# 8x_LED_Trieber_Stage_01.net
KiCad netlist of a schematic drawn in EAGLE
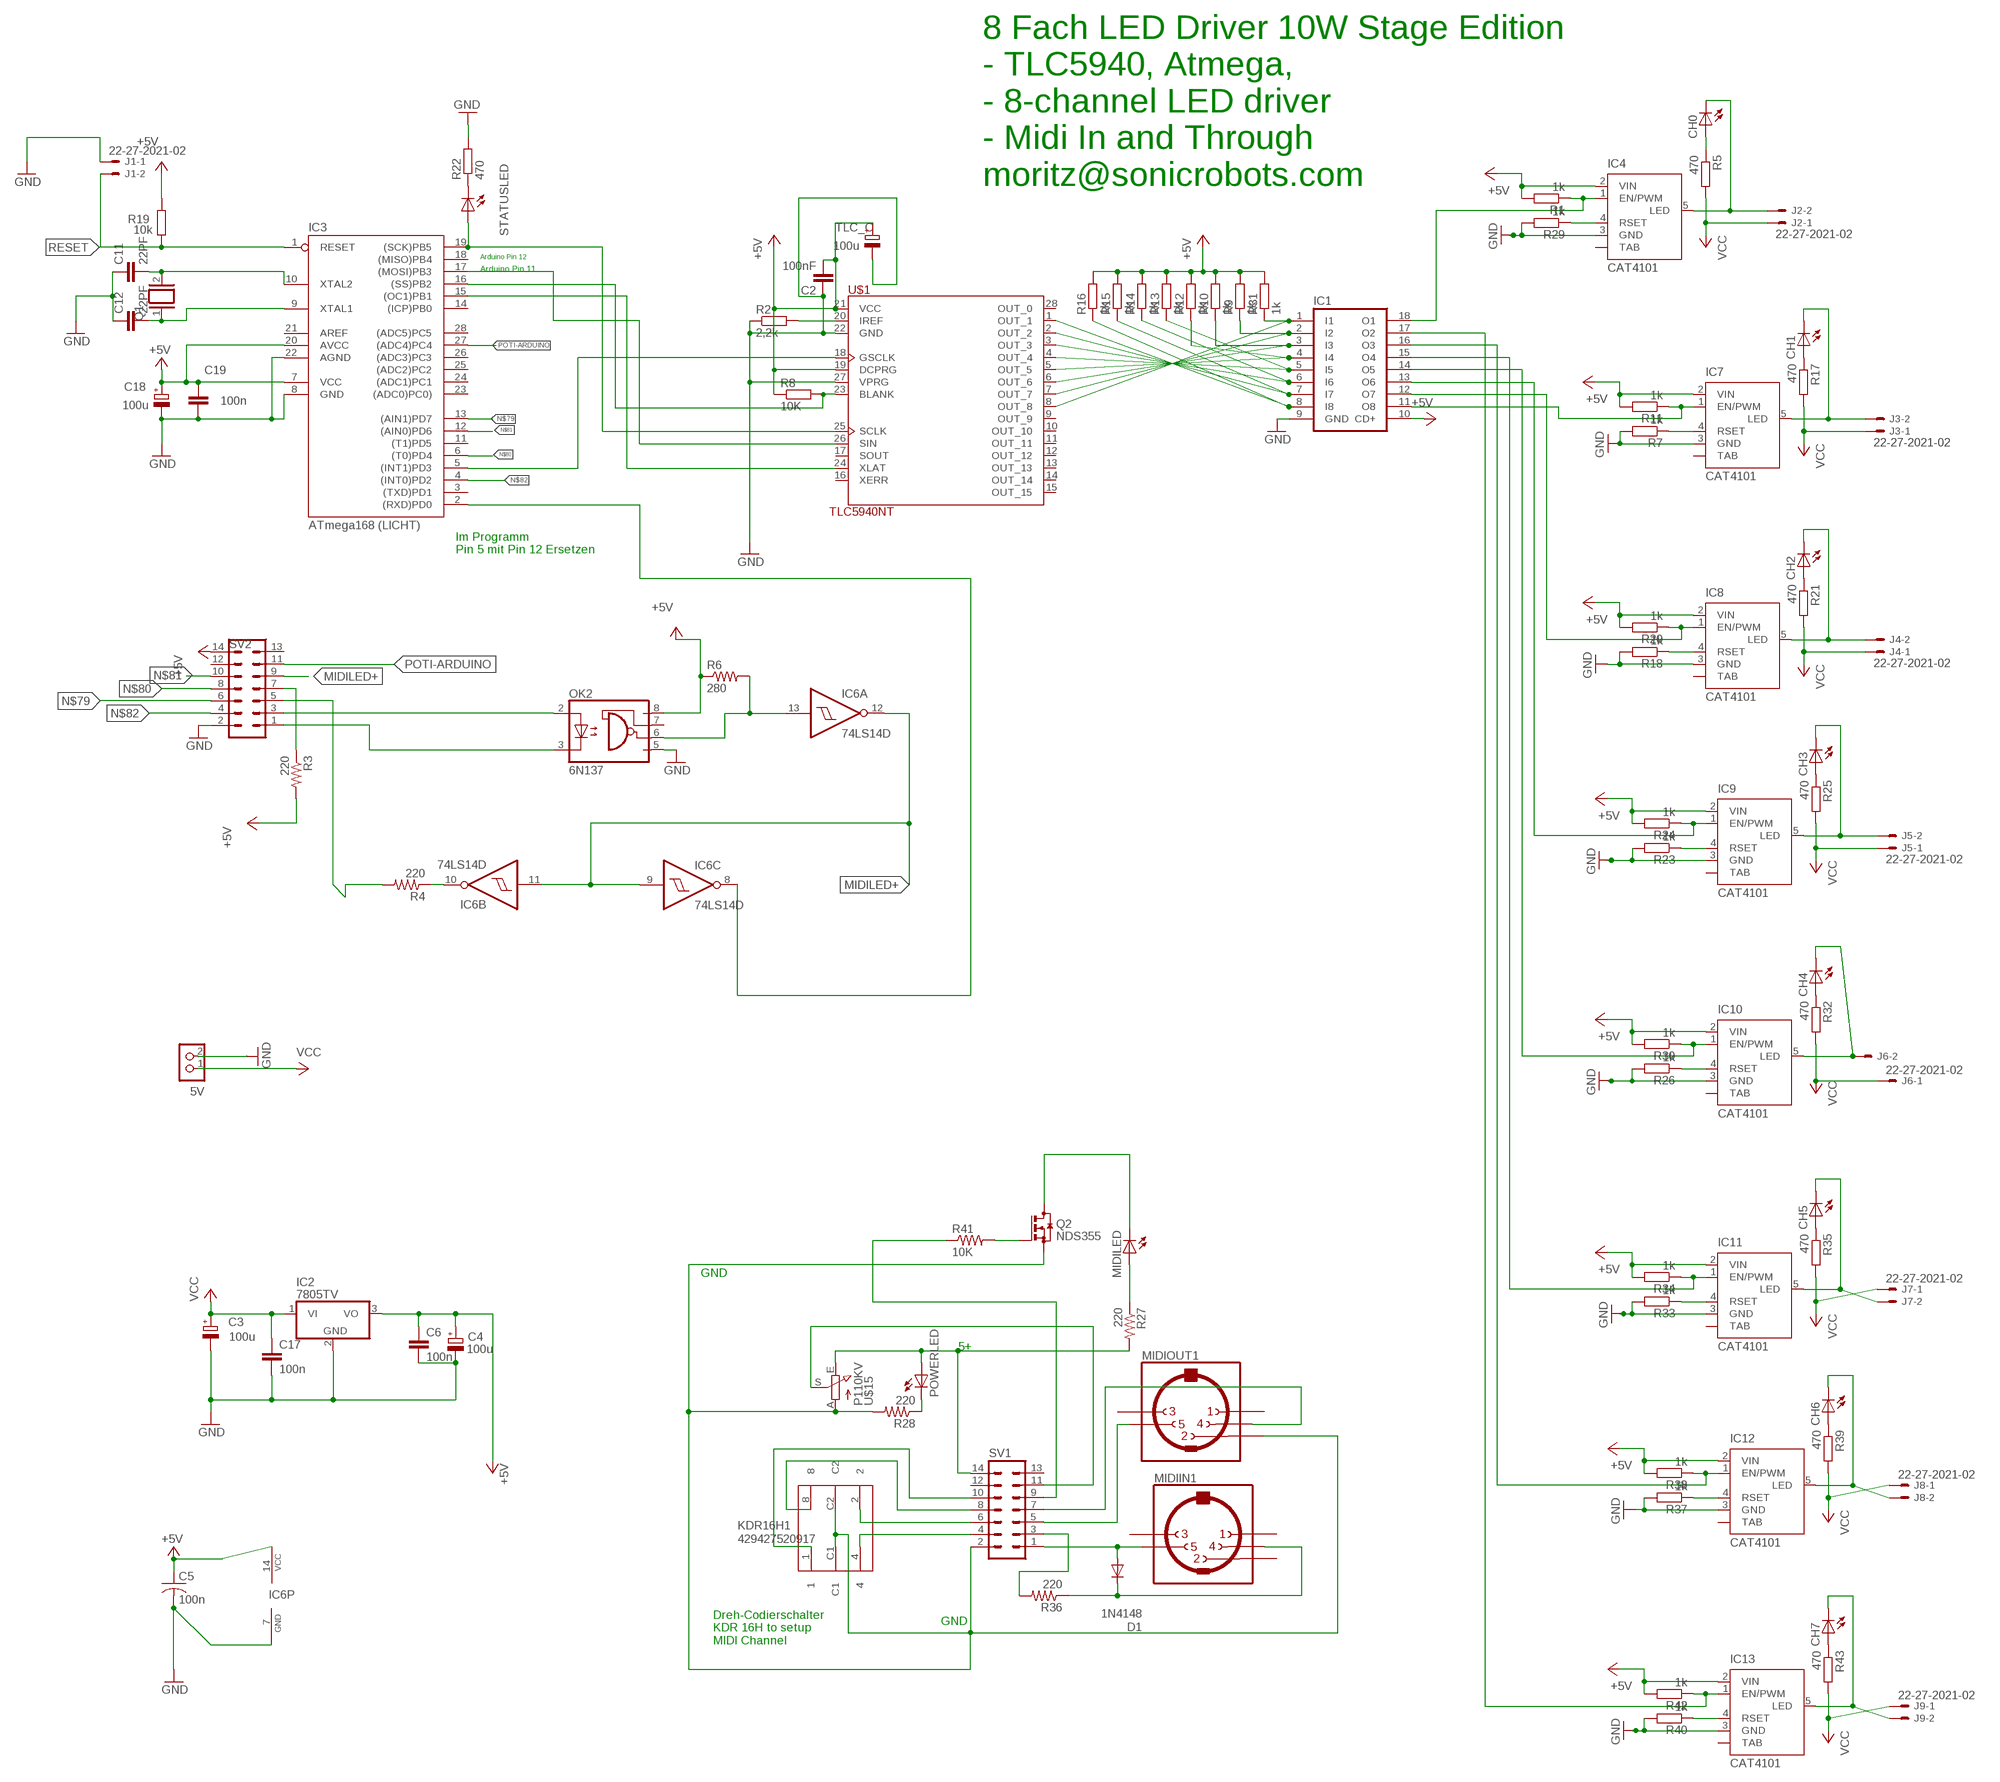
[diagram p0: schematic, sheet 1]

(export (version "E")
  (design (tool "Eeschema 10.0.6"))
  (components
    (comp (ref "5V")
      (value "5V")
      (footprint "eagle-import:TERMINAL_BLOCK_2P_5")
      (libsource (lib "eagle-import") (part "CON_TERMINAL_BLOCK_02-5MM"))
    )
    (comp (ref "C2")
      (value "100nF")
      (footprint "eagle-import:C0805")
      (libsource (lib "eagle-import") (part "rcl_C-EUC0805"))
    )
    (comp (ref "C3")
      (value "100u")
      (footprint "eagle-import:E2,5-6")
      (libsource (lib "eagle-import") (part "CPOL-EUE2.5-6"))
    )
    (comp (ref "C4")
      (value "100u")
      (footprint "eagle-import:E2,5-6")
      (libsource (lib "eagle-import") (part "CPOL-EUE2.5-6"))
    )
    (comp (ref "C5")
      (value "100n")
      (footprint "eagle-import:C0805")
      (libsource (lib "eagle-import") (part "C-USC0805"))
    )
    (comp (ref "C6")
      (value "100n")
      (footprint "eagle-import:C0805K")
      (libsource (lib "eagle-import") (part "C-EUC0805K"))
    )
    (comp (ref "C11")
      (value "22PF")
      (footprint "eagle-import:C0805")
      (libsource (lib "eagle-import") (part "rcl_C-EUC0805"))
    )
    (comp (ref "C12")
      (value "22PF")
      (footprint "eagle-import:C0805")
      (libsource (lib "eagle-import") (part "rcl_C-EUC0805"))
    )
    (comp (ref "C17")
      (value "100n")
      (footprint "eagle-import:C0805K")
      (libsource (lib "eagle-import") (part "C-EUC0805K"))
    )
    (comp (ref "C18")
      (value "100u")
      (footprint "eagle-import:E2,5-6")
      (libsource (lib "eagle-import") (part "CPOL-EUE2.5-6"))
    )
    (comp (ref "C19")
      (value "100n")
      (footprint "eagle-import:C0805K")
      (libsource (lib "eagle-import") (part "C-EUC0805K"))
    )
    (comp (ref "CH0")
      (value "LED3MM")
      (footprint "eagle-import:LED3MM")
      (libsource (lib "eagle-import") (part "LED3MM"))
    )
    (comp (ref "CH1")
      (value "LED3MM")
      (footprint "eagle-import:LED3MM")
      (libsource (lib "eagle-import") (part "LED3MM"))
    )
    (comp (ref "CH2")
      (value "LED3MM")
      (footprint "eagle-import:LED3MM")
      (libsource (lib "eagle-import") (part "LED3MM"))
    )
    (comp (ref "CH3")
      (value "LED3MM")
      (footprint "eagle-import:LED3MM")
      (libsource (lib "eagle-import") (part "LED3MM"))
    )
    (comp (ref "CH4")
      (value "LED3MM")
      (footprint "eagle-import:LED3MM")
      (libsource (lib "eagle-import") (part "LED3MM"))
    )
    (comp (ref "CH5")
      (value "LED3MM")
      (footprint "eagle-import:LED3MM")
      (libsource (lib "eagle-import") (part "LED3MM"))
    )
    (comp (ref "CH6")
      (value "LED3MM")
      (footprint "eagle-import:LED3MM")
      (libsource (lib "eagle-import") (part "LED3MM"))
    )
    (comp (ref "CH7")
      (value "LED3MM")
      (footprint "eagle-import:LED3MM")
      (libsource (lib "eagle-import") (part "LED3MM"))
    )
    (comp (ref "D1")
      (value "1N4148")
      (footprint "eagle-import:D-7.5")
      (libsource (lib "eagle-import") (part "DIODE-D-7.5"))
    )
    (comp (ref "IC1")
      (value "IC_ULN2803AN")
      (footprint "eagle-import:DIL18")
      (libsource (lib "eagle-import") (part "IC_ULN2803AN"))
    )
    (comp (ref "IC2")
      (value "7805TV")
      (footprint "eagle-import:TO220V")
      (libsource (lib "eagle-import") (part "78TV05"))
    )
    (comp (ref "IC3")
      (value "ATmega168 (LICHT)")
      (footprint "eagle-import:DIL28-3")
      (libsource (lib "eagle-import") (part "AT90S4433P"))
    )
    (comp (ref "IC4")
      (value "CAT4101")
      (footprint "eagle-import:TO263_5")
      (fields (field (name "MPN") "CAT4101TV-T75"))
      (libsource (lib "eagle-import") (part "CAT4101"))
    )
    (comp (ref "IC6")
      (value "74LS14D")
      (footprint "eagle-import:SO14")
      (libsource (lib "eagle-import") (part "7414DLS"))
    )
    (comp (ref "IC7")
      (value "CAT4101")
      (footprint "eagle-import:TO263_5")
      (fields (field (name "MPN") "CAT4101TV-T75"))
      (libsource (lib "eagle-import") (part "CAT4101"))
    )
    (comp (ref "IC8")
      (value "CAT4101")
      (footprint "eagle-import:TO263_5")
      (fields (field (name "MPN") "CAT4101TV-T75"))
      (libsource (lib "eagle-import") (part "CAT4101"))
    )
    (comp (ref "IC9")
      (value "CAT4101")
      (footprint "eagle-import:TO263_5")
      (fields (field (name "MPN") "CAT4101TV-T75"))
      (libsource (lib "eagle-import") (part "CAT4101"))
    )
    (comp (ref "IC10")
      (value "CAT4101")
      (footprint "eagle-import:TO263_5")
      (fields (field (name "MPN") "CAT4101TV-T75"))
      (libsource (lib "eagle-import") (part "CAT4101"))
    )
    (comp (ref "IC11")
      (value "CAT4101")
      (footprint "eagle-import:TO263_5")
      (fields (field (name "MPN") "CAT4101TV-T75"))
      (libsource (lib "eagle-import") (part "CAT4101"))
    )
    (comp (ref "IC12")
      (value "CAT4101")
      (footprint "eagle-import:TO263_5")
      (fields (field (name "MPN") "CAT4101TV-T75"))
      (libsource (lib "eagle-import") (part "CAT4101"))
    )
    (comp (ref "IC13")
      (value "CAT4101")
      (footprint "eagle-import:TO263_5")
      (fields (field (name "MPN") "CAT4101TV-T75"))
      (libsource (lib "eagle-import") (part "CAT4101"))
    )
    (comp (ref "J1")
      (value "22-27-2021-02")
      (footprint "eagle-import:6410-02")
      (libsource (lib "eagle-import") (part "22-?-0227-2021"))
    )
    (comp (ref "J2")
      (value "22-27-2021-02")
      (footprint "eagle-import:6410-02")
      (libsource (lib "eagle-import") (part "22-?-0227-2021"))
    )
    (comp (ref "J3")
      (value "22-27-2021-02")
      (footprint "eagle-import:6410-02")
      (libsource (lib "eagle-import") (part "22-?-0227-2021"))
    )
    (comp (ref "J4")
      (value "22-27-2021-02")
      (footprint "eagle-import:6410-02")
      (libsource (lib "eagle-import") (part "22-?-0227-2021"))
    )
    (comp (ref "J5")
      (value "22-27-2021-02")
      (footprint "eagle-import:6410-02")
      (libsource (lib "eagle-import") (part "22-?-0227-2021"))
    )
    (comp (ref "J6")
      (value "22-27-2021-02")
      (footprint "eagle-import:6410-02")
      (libsource (lib "eagle-import") (part "22-?-0227-2021"))
    )
    (comp (ref "J7")
      (value "22-27-2021-02")
      (footprint "eagle-import:6410-02")
      (libsource (lib "eagle-import") (part "22-?-0227-2021"))
    )
    (comp (ref "J8")
      (value "22-27-2021-02")
      (footprint "eagle-import:6410-02")
      (libsource (lib "eagle-import") (part "22-?-0227-2021"))
    )
    (comp (ref "J9")
      (value "22-27-2021-02")
      (footprint "eagle-import:6410-02")
      (libsource (lib "eagle-import") (part "22-?-0227-2021"))
    )
    (comp (ref "KDR16H1")
      (value "429427520917")
      (footprint "eagle-import:429427520917")
      (libsource (lib "eagle-import") (part "429427520917"))
    )
    (comp (ref "MIDIIN1")
      (value "MAB5SH")
      (footprint "eagle-import:MAB5SH")
      (libsource (lib "eagle-import") (part "MAB5SH"))
    )
    (comp (ref "MIDILED")
      (value "LED3MM")
      (footprint "eagle-import:LED3MM")
      (libsource (lib "eagle-import") (part "LED3MM"))
    )
    (comp (ref "MIDIOUT1")
      (value "MAB5SH")
      (footprint "eagle-import:MAB5SH")
      (libsource (lib "eagle-import") (part "MAB5SH"))
    )
    (comp (ref "OK2")
      (value "6N137")
      (footprint "eagle-import:DIL08")
      (fields
        (field (name "MPN") "6N137")
        (field (name "OC_FARNELL") "1328376")
        (field (name "OC_NEWARK") "52M1895")
      )
      (libsource (lib "eagle-import") (part "6N137"))
    )
    (comp (ref "POWERLED")
      (value "LED3MM")
      (footprint "eagle-import:LED3MM")
      (libsource (lib "eagle-import") (part "LED3MM"))
    )
    (comp (ref "Q1")
      (value "XTAL/S")
      (footprint "eagle-import:QS")
      (libsource (lib "eagle-import") (part "XTAL/S"))
    )
    (comp (ref "Q2")
      (value "NDS355")
      (footprint "eagle-import:SOT23")
      (libsource (lib "eagle-import") (part "BSS123"))
    )
    (comp (ref "R1")
      (value "1k")
      (footprint "eagle-import:R0805W")
      (libsource (lib "eagle-import") (part "R-EU_R0805W"))
    )
    (comp (ref "R2")
      (value "2,2k")
      (footprint "eagle-import:R0805")
      (libsource (lib "eagle-import") (part "R-EU_R0805"))
    )
    (comp (ref "R3")
      (value "220")
      (footprint "eagle-import:R0805")
      (libsource (lib "eagle-import") (part "R-US_R0805"))
    )
    (comp (ref "R4")
      (value "220")
      (footprint "eagle-import:R0805")
      (libsource (lib "eagle-import") (part "R-US_R0805"))
    )
    (comp (ref "R5")
      (value "470")
      (footprint "eagle-import:M0805")
      (libsource (lib "eagle-import") (part "R-EU_M0805"))
    )
    (comp (ref "R6")
      (value "280")
      (footprint "eagle-import:R0805")
      (libsource (lib "eagle-import") (part "R-US_R0805"))
    )
    (comp (ref "R7")
      (value "1k")
      (footprint "eagle-import:R0805W")
      (libsource (lib "eagle-import") (part "R-EU_R0805W"))
    )
    (comp (ref "R8")
      (value "10K")
      (footprint "eagle-import:R0805")
      (libsource (lib "eagle-import") (part "R-EU_R0805"))
    )
    (comp (ref "R9")
      (value "1k")
      (footprint "eagle-import:R0805W")
      (libsource (lib "eagle-import") (part "R-EU_R0805W"))
    )
    (comp (ref "R10")
      (value "1k")
      (footprint "eagle-import:R0805W")
      (libsource (lib "eagle-import") (part "R-EU_R0805W"))
    )
    (comp (ref "R11")
      (value "1k")
      (footprint "eagle-import:R0805W")
      (libsource (lib "eagle-import") (part "R-EU_R0805W"))
    )
    (comp (ref "R12")
      (value "1k")
      (footprint "eagle-import:R0805W")
      (libsource (lib "eagle-import") (part "R-EU_R0805W"))
    )
    (comp (ref "R13")
      (value "1k")
      (footprint "eagle-import:R0805W")
      (libsource (lib "eagle-import") (part "R-EU_R0805W"))
    )
    (comp (ref "R14")
      (value "1k")
      (footprint "eagle-import:R0805W")
      (libsource (lib "eagle-import") (part "R-EU_R0805W"))
    )
    (comp (ref "R15")
      (value "1k")
      (footprint "eagle-import:R0805W")
      (libsource (lib "eagle-import") (part "R-EU_R0805W"))
    )
    (comp (ref "R16")
      (value "1k")
      (footprint "eagle-import:R0805W")
      (libsource (lib "eagle-import") (part "R-EU_R0805W"))
    )
    (comp (ref "R17")
      (value "470")
      (footprint "eagle-import:M0805")
      (libsource (lib "eagle-import") (part "R-EU_M0805"))
    )
    (comp (ref "R18")
      (value "1k")
      (footprint "eagle-import:R0805W")
      (libsource (lib "eagle-import") (part "R-EU_R0805W"))
    )
    (comp (ref "R19")
      (value "10k")
      (footprint "eagle-import:R0805")
      (libsource (lib "eagle-import") (part "R-EU_R0805"))
    )
    (comp (ref "R20")
      (value "1k")
      (footprint "eagle-import:R0805W")
      (libsource (lib "eagle-import") (part "R-EU_R0805W"))
    )
    (comp (ref "R21")
      (value "470")
      (footprint "eagle-import:M0805")
      (libsource (lib "eagle-import") (part "R-EU_M0805"))
    )
    (comp (ref "R22")
      (value "470")
      (footprint "eagle-import:M0805")
      (libsource (lib "eagle-import") (part "R-EU_M0805"))
    )
    (comp (ref "R23")
      (value "1k")
      (footprint "eagle-import:R0805W")
      (libsource (lib "eagle-import") (part "R-EU_R0805W"))
    )
    (comp (ref "R24")
      (value "1k")
      (footprint "eagle-import:R0805W")
      (libsource (lib "eagle-import") (part "R-EU_R0805W"))
    )
    (comp (ref "R25")
      (value "470")
      (footprint "eagle-import:M0805")
      (libsource (lib "eagle-import") (part "R-EU_M0805"))
    )
    (comp (ref "R26")
      (value "1k")
      (footprint "eagle-import:R0805W")
      (libsource (lib "eagle-import") (part "R-EU_R0805W"))
    )
    (comp (ref "R27")
      (value "220")
      (footprint "eagle-import:R0805W")
      (libsource (lib "eagle-import") (part "R-US_R0805W"))
    )
    (comp (ref "R28")
      (value "220")
      (footprint "eagle-import:R0805")
      (libsource (lib "eagle-import") (part "R-US_R0805"))
    )
    (comp (ref "R29")
      (value "1k")
      (footprint "eagle-import:R0805W")
      (libsource (lib "eagle-import") (part "R-EU_R0805W"))
    )
    (comp (ref "R30")
      (value "1k")
      (footprint "eagle-import:R0805W")
      (libsource (lib "eagle-import") (part "R-EU_R0805W"))
    )
    (comp (ref "R31")
      (value "1k")
      (footprint "eagle-import:R0805W")
      (libsource (lib "eagle-import") (part "R-EU_R0805W"))
    )
    (comp (ref "R32")
      (value "470")
      (footprint "eagle-import:M0805")
      (libsource (lib "eagle-import") (part "R-EU_M0805"))
    )
    (comp (ref "R33")
      (value "1k")
      (footprint "eagle-import:R0805W")
      (libsource (lib "eagle-import") (part "R-EU_R0805W"))
    )
    (comp (ref "R34")
      (value "1k")
      (footprint "eagle-import:R0805W")
      (libsource (lib "eagle-import") (part "R-EU_R0805W"))
    )
    (comp (ref "R35")
      (value "470")
      (footprint "eagle-import:M0805")
      (libsource (lib "eagle-import") (part "R-EU_M0805"))
    )
    (comp (ref "R36")
      (value "220")
      (footprint "eagle-import:R0805")
      (libsource (lib "eagle-import") (part "R-US_R0805"))
    )
    (comp (ref "R37")
      (value "1k")
      (footprint "eagle-import:R0805W")
      (libsource (lib "eagle-import") (part "R-EU_R0805W"))
    )
    (comp (ref "R38")
      (value "1k")
      (footprint "eagle-import:R0805W")
      (libsource (lib "eagle-import") (part "R-EU_R0805W"))
    )
    (comp (ref "R39")
      (value "470")
      (footprint "eagle-import:M0805")
      (libsource (lib "eagle-import") (part "R-EU_M0805"))
    )
    (comp (ref "R40")
      (value "1k")
      (footprint "eagle-import:R0805W")
      (libsource (lib "eagle-import") (part "R-EU_R0805W"))
    )
    (comp (ref "R41")
      (value "10K")
      (footprint "eagle-import:R0805")
      (libsource (lib "eagle-import") (part "R-US_R0805"))
    )
    (comp (ref "R42")
      (value "1k")
      (footprint "eagle-import:R0805W")
      (libsource (lib "eagle-import") (part "R-EU_R0805W"))
    )
    (comp (ref "R43")
      (value "470")
      (footprint "eagle-import:M0805")
      (libsource (lib "eagle-import") (part "R-EU_M0805"))
    )
    (comp (ref "STATUSLED")
      (value "LED3MM")
      (footprint "eagle-import:LED3MM")
      (libsource (lib "eagle-import") (part "LED3MM"))
    )
    (comp (ref "SV1")
      (value "ML14")
      (footprint "eagle-import:ML14")
      (libsource (lib "eagle-import") (part "ML14"))
    )
    (comp (ref "SV2")
      (value "ML14")
      (footprint "eagle-import:ML14")
      (libsource (lib "eagle-import") (part "ML14"))
    )
    (comp (ref "TLC_C")
      (value "100u")
      (footprint "eagle-import:E2,5-6")
      (libsource (lib "eagle-import") (part "CPOL-EUE2.5-6"))
    )
    (comp (ref "U$1")
      (value "TLC5940NT")
      (footprint "eagle-import:DIP-28")
      (libsource (lib "eagle-import") (part "TLC5940NT"))
    )
    (comp (ref "U$15")
      (value "P110KV")
      (footprint "eagle-import:POT-P110KV")
      (libsource (lib "eagle-import") (part "P110KV"))
    )
  )
  (nets
    (net (code "1") (name "+5V") (class "Default")
      (node (ref "C18") (pin "+") (pinfunction "+_+") (pintype "passive"))
      (node (ref "C19") (pin "1") (pinfunction "1_1") (pintype "passive"))
      (node (ref "C2") (pin "2") (pinfunction "2_2") (pintype "passive"))
      (node (ref "C4") (pin "+") (pinfunction "+_+") (pintype "passive"))
      (node (ref "C5") (pin "1") (pinfunction "1_1") (pintype "passive"))
      (node (ref "C6") (pin "1") (pinfunction "1_1") (pintype "passive"))
      (node (ref "IC1") (pin "10") (pinfunction "CD+_10") (pintype "passive"))
      (node (ref "IC10") (pin "2") (pinfunction "VIN_2") (pintype "input"))
      (node (ref "IC11") (pin "2") (pinfunction "VIN_2") (pintype "input"))
      (node (ref "IC12") (pin "2") (pinfunction "VIN_2") (pintype "input"))
      (node (ref "IC13") (pin "2") (pinfunction "VIN_2") (pintype "input"))
      (node (ref "IC2") (pin "3") (pinfunction "VO_3") (pintype "passive"))
      (node (ref "IC3") (pin "20") (pinfunction "AVCC_20") (pintype "power_in"))
      (node (ref "IC3") (pin "7") (pinfunction "VCC_7") (pintype "power_in"))
      (node (ref "IC4") (pin "2") (pinfunction "VIN_2") (pintype "input"))
      (node (ref "IC6") (pin "14") (pinfunction "VCC_14") (pintype "power_in"))
      (node (ref "IC7") (pin "2") (pinfunction "VIN_2") (pintype "input"))
      (node (ref "IC8") (pin "2") (pinfunction "VIN_2") (pintype "input"))
      (node (ref "IC9") (pin "2") (pinfunction "VIN_2") (pintype "input"))
      (node (ref "OK2") (pin "8") (pinfunction "VCC_8") (pintype "passive"))
      (node (ref "R1") (pin "2") (pinfunction "2_2") (pintype "passive"))
      (node (ref "R10") (pin "2") (pinfunction "2_2") (pintype "passive"))
      (node (ref "R11") (pin "2") (pinfunction "2_2") (pintype "passive"))
      (node (ref "R12") (pin "2") (pinfunction "2_2") (pintype "passive"))
      (node (ref "R13") (pin "2") (pinfunction "2_2") (pintype "passive"))
      (node (ref "R14") (pin "2") (pinfunction "2_2") (pintype "passive"))
      (node (ref "R15") (pin "2") (pinfunction "2_2") (pintype "passive"))
      (node (ref "R16") (pin "2") (pinfunction "2_2") (pintype "passive"))
      (node (ref "R19") (pin "2") (pinfunction "2_2") (pintype "passive"))
      (node (ref "R20") (pin "2") (pinfunction "2_2") (pintype "passive"))
      (node (ref "R24") (pin "2") (pinfunction "2_2") (pintype "passive"))
      (node (ref "R3") (pin "2") (pinfunction "2_2") (pintype "passive"))
      (node (ref "R30") (pin "2") (pinfunction "2_2") (pintype "passive"))
      (node (ref "R31") (pin "2") (pinfunction "2_2") (pintype "passive"))
      (node (ref "R34") (pin "2") (pinfunction "2_2") (pintype "passive"))
      (node (ref "R38") (pin "2") (pinfunction "2_2") (pintype "passive"))
      (node (ref "R42") (pin "2") (pinfunction "2_2") (pintype "passive"))
      (node (ref "R6") (pin "1") (pinfunction "1_1") (pintype "passive"))
      (node (ref "R8") (pin "1") (pinfunction "1_1") (pintype "passive"))
      (node (ref "R9") (pin "2") (pinfunction "2_2") (pintype "passive"))
      (node (ref "SV2") (pin "14") (pinfunction "14_14") (pintype "passive"))
      (node (ref "TLC_C") (pin "+") (pinfunction "+_+") (pintype "passive"))
      (node (ref "U$1") (pin "19") (pinfunction "DCPRG_19") (pintype "input"))
      (node (ref "U$1") (pin "21") (pinfunction "VCC_21") (pintype "power_in"))
    )
    (net (code "2") (name "GND") (class "Default")
      (node (ref "5V") (pin "2") (pinfunction "2_2") (pintype "passive"))
      (node (ref "C11") (pin "1") (pinfunction "1_1") (pintype "passive"))
      (node (ref "C12") (pin "1") (pinfunction "1_1") (pintype "passive"))
      (node (ref "C17") (pin "2") (pinfunction "2_2") (pintype "passive"))
      (node (ref "C18") (pin "-") (pinfunction "-_-") (pintype "passive"))
      (node (ref "C19") (pin "2") (pinfunction "2_2") (pintype "passive"))
      (node (ref "C2") (pin "1") (pinfunction "1_1") (pintype "passive"))
      (node (ref "C3") (pin "-") (pinfunction "-_-") (pintype "passive"))
      (node (ref "C4") (pin "-") (pinfunction "-_-") (pintype "passive"))
      (node (ref "C5") (pin "2") (pinfunction "2_2") (pintype "passive"))
      (node (ref "C6") (pin "2") (pinfunction "2_2") (pintype "passive"))
      (node (ref "IC1") (pin "9") (pinfunction "GND_9") (pintype "power_in"))
      (node (ref "IC10") (pin "3") (pinfunction "GND_3") (pintype "power_in"))
      (node (ref "IC11") (pin "3") (pinfunction "GND_3") (pintype "power_in"))
      (node (ref "IC12") (pin "3") (pinfunction "GND_3") (pintype "power_in"))
      (node (ref "IC13") (pin "3") (pinfunction "GND_3") (pintype "power_in"))
      (node (ref "IC2") (pin "2") (pinfunction "GND_2") (pintype "passive"))
      (node (ref "IC3") (pin "22") (pinfunction "AGND_22") (pintype "power_in"))
      (node (ref "IC3") (pin "8") (pinfunction "GND_8") (pintype "power_in"))
      (node (ref "IC4") (pin "3") (pinfunction "GND_3") (pintype "power_in"))
      (node (ref "IC6") (pin "7") (pinfunction "GND_7") (pintype "power_in"))
      (node (ref "IC7") (pin "3") (pinfunction "GND_3") (pintype "power_in"))
      (node (ref "IC8") (pin "3") (pinfunction "GND_3") (pintype "power_in"))
      (node (ref "IC9") (pin "3") (pinfunction "GND_3") (pintype "power_in"))
      (node (ref "J1") (pin "1") (pinfunction "S_1") (pintype "passive"))
      (node (ref "OK2") (pin "5") (pinfunction "GND_5") (pintype "passive"))
      (node (ref "R18") (pin "2") (pinfunction "2_2") (pintype "passive"))
      (node (ref "R2") (pin "1") (pinfunction "1_1") (pintype "passive"))
      (node (ref "R22") (pin "2") (pinfunction "2_2") (pintype "passive"))
      (node (ref "R23") (pin "2") (pinfunction "2_2") (pintype "passive"))
      (node (ref "R26") (pin "2") (pinfunction "2_2") (pintype "passive"))
      (node (ref "R29") (pin "2") (pinfunction "2_2") (pintype "passive"))
      (node (ref "R33") (pin "2") (pinfunction "2_2") (pintype "passive"))
      (node (ref "R37") (pin "2") (pinfunction "2_2") (pintype "passive"))
      (node (ref "R40") (pin "2") (pinfunction "2_2") (pintype "passive"))
      (node (ref "R7") (pin "2") (pinfunction "2_2") (pintype "passive"))
      (node (ref "SV2") (pin "2") (pinfunction "2_2") (pintype "passive"))
      (node (ref "TLC_C") (pin "-") (pinfunction "-_-") (pintype "passive"))
      (node (ref "U$1") (pin "22") (pinfunction "GND_22") (pintype "power_in"))
      (node (ref "U$1") (pin "27") (pinfunction "VPRG_27") (pintype "input"))
    )
    (net (code "3") (name "MIDILED+") (class "Default")
      (node (ref "IC6") (pin "11") (pinfunction "I_11") (pintype "input"))
      (node (ref "IC6") (pin "12") (pinfunction "O_12") (pintype "output"))
      (node (ref "IC6") (pin "9") (pinfunction "I_9") (pintype "input"))
      (node (ref "SV2") (pin "9") (pinfunction "9_9") (pintype "passive"))
    )
    (net (code "4") (name "N$79") (class "Default")
      (node (ref "IC3") (pin "13") (pinfunction "(AIN1)PD7_13") (pintype "bidirectional"))
      (node (ref "SV2") (pin "6") (pinfunction "6_6") (pintype "passive"))
    )
    (net (code "5") (name "N$80") (class "Default")
      (node (ref "IC3") (pin "6") (pinfunction "(T0)PD4_6") (pintype "bidirectional"))
      (node (ref "SV2") (pin "8") (pinfunction "8_8") (pintype "passive"))
    )
    (net (code "6") (name "N$81") (class "Default")
      (node (ref "IC3") (pin "12") (pinfunction "(AIN0)PD6_12") (pintype "bidirectional"))
      (node (ref "SV2") (pin "10") (pinfunction "10_10") (pintype "passive"))
    )
    (net (code "7") (name "N$82") (class "Default")
      (node (ref "IC3") (pin "4") (pinfunction "(INT0)PD2_4") (pintype "bidirectional"))
      (node (ref "SV2") (pin "4") (pinfunction "4_4") (pintype "passive"))
    )
    (net (code "8") (name "Net-(CH0-C)") (class "Default")
      (node (ref "CH0") (pin "K") (pinfunction "C_K") (pintype "passive"))
      (node (ref "IC4") (pin "5") (pinfunction "LED_5") (pintype "power_in"))
      (node (ref "J2") (pin "2") (pinfunction "S_2") (pintype "passive"))
    )
    (net (code "9") (name "Net-(CH0-PadA)") (class "Default")
      (node (ref "CH0") (pin "A") (pinfunction "A_A") (pintype "passive"))
      (node (ref "R5") (pin "1") (pinfunction "1_1") (pintype "passive"))
    )
    (net (code "10") (name "Net-(CH1-C)") (class "Default")
      (node (ref "CH1") (pin "K") (pinfunction "C_K") (pintype "passive"))
      (node (ref "IC7") (pin "5") (pinfunction "LED_5") (pintype "power_in"))
      (node (ref "J3") (pin "2") (pinfunction "S_2") (pintype "passive"))
    )
    (net (code "11") (name "Net-(CH1-PadA)") (class "Default")
      (node (ref "CH1") (pin "A") (pinfunction "A_A") (pintype "passive"))
      (node (ref "R17") (pin "1") (pinfunction "1_1") (pintype "passive"))
    )
    (net (code "12") (name "Net-(CH2-C)") (class "Default")
      (node (ref "CH2") (pin "K") (pinfunction "C_K") (pintype "passive"))
      (node (ref "IC8") (pin "5") (pinfunction "LED_5") (pintype "power_in"))
      (node (ref "J4") (pin "2") (pinfunction "S_2") (pintype "passive"))
    )
    (net (code "13") (name "Net-(CH2-PadA)") (class "Default")
      (node (ref "CH2") (pin "A") (pinfunction "A_A") (pintype "passive"))
      (node (ref "R21") (pin "1") (pinfunction "1_1") (pintype "passive"))
    )
    (net (code "14") (name "Net-(CH3-C)") (class "Default")
      (node (ref "CH3") (pin "K") (pinfunction "C_K") (pintype "passive"))
      (node (ref "IC9") (pin "5") (pinfunction "LED_5") (pintype "power_in"))
      (node (ref "J5") (pin "2") (pinfunction "S_2") (pintype "passive"))
    )
    (net (code "15") (name "Net-(CH3-PadA)") (class "Default")
      (node (ref "CH3") (pin "A") (pinfunction "A_A") (pintype "passive"))
      (node (ref "R25") (pin "1") (pinfunction "1_1") (pintype "passive"))
    )
    (net (code "16") (name "Net-(CH4-C)") (class "Default")
      (node (ref "CH4") (pin "K") (pinfunction "C_K") (pintype "passive"))
      (node (ref "IC10") (pin "5") (pinfunction "LED_5") (pintype "power_in"))
      (node (ref "J6") (pin "2") (pinfunction "S_2") (pintype "passive"))
    )
    (net (code "17") (name "Net-(CH4-PadA)") (class "Default")
      (node (ref "CH4") (pin "A") (pinfunction "A_A") (pintype "passive"))
      (node (ref "R32") (pin "1") (pinfunction "1_1") (pintype "passive"))
    )
    (net (code "18") (name "Net-(CH5-C)") (class "Default")
      (node (ref "CH5") (pin "K") (pinfunction "C_K") (pintype "passive"))
      (node (ref "IC11") (pin "5") (pinfunction "LED_5") (pintype "power_in"))
      (node (ref "J7") (pin "2") (pinfunction "S_2") (pintype "passive"))
    )
    (net (code "19") (name "Net-(CH5-PadA)") (class "Default")
      (node (ref "CH5") (pin "A") (pinfunction "A_A") (pintype "passive"))
      (node (ref "R35") (pin "1") (pinfunction "1_1") (pintype "passive"))
    )
    (net (code "20") (name "Net-(CH6-C)") (class "Default")
      (node (ref "CH6") (pin "K") (pinfunction "C_K") (pintype "passive"))
      (node (ref "IC12") (pin "5") (pinfunction "LED_5") (pintype "power_in"))
      (node (ref "J8") (pin "2") (pinfunction "S_2") (pintype "passive"))
    )
    (net (code "21") (name "Net-(CH6-PadA)") (class "Default")
      (node (ref "CH6") (pin "A") (pinfunction "A_A") (pintype "passive"))
      (node (ref "R39") (pin "1") (pinfunction "1_1") (pintype "passive"))
    )
    (net (code "22") (name "Net-(CH7-C)") (class "Default")
      (node (ref "CH7") (pin "K") (pinfunction "C_K") (pintype "passive"))
      (node (ref "IC13") (pin "5") (pinfunction "LED_5") (pintype "power_in"))
      (node (ref "J9") (pin "2") (pinfunction "S_2") (pintype "passive"))
    )
    (net (code "23") (name "Net-(CH7-PadA)") (class "Default")
      (node (ref "CH7") (pin "A") (pinfunction "A_A") (pintype "passive"))
      (node (ref "R43") (pin "1") (pinfunction "1_1") (pintype "passive"))
    )
    (net (code "24") (name "Net-(D1-PadA)") (class "Default")
      (node (ref "D1") (pin "A") (pinfunction "A_A") (pintype "passive"))
      (node (ref "MIDIIN1") (pin "5") (pinfunction "5_5") (pintype "passive"))
      (node (ref "SV1") (pin "1") (pinfunction "1_1") (pintype "passive"))
    )
    (net (code "25") (name "Net-(D1-PadC)") (class "Default")
      (node (ref "D1") (pin "C") (pinfunction "C_C") (pintype "passive"))
      (node (ref "MIDIIN1") (pin "4") (pinfunction "4_4") (pintype "passive"))
      (node (ref "R36") (pin "1") (pinfunction "1_1") (pintype "passive"))
    )
    (net (code "26") (name "Net-(IC1-I1)") (class "Default")
      (node (ref "IC1") (pin "1") (pinfunction "I1_1") (pintype "input"))
      (node (ref "R31") (pin "1") (pinfunction "1_1") (pintype "passive"))
      (node (ref "U$1") (pin "8") (pinfunction "OUT_8_8") (pintype "output"))
    )
    (net (code "27") (name "Net-(IC1-I2)") (class "Default")
      (node (ref "IC1") (pin "2") (pinfunction "I2_2") (pintype "input"))
      (node (ref "R9") (pin "1") (pinfunction "1_1") (pintype "passive"))
      (node (ref "U$1") (pin "7") (pinfunction "OUT_7_7") (pintype "output"))
    )
    (net (code "28") (name "Net-(IC1-I3)") (class "Default")
      (node (ref "IC1") (pin "3") (pinfunction "I3_3") (pintype "input"))
      (node (ref "R10") (pin "1") (pinfunction "1_1") (pintype "passive"))
      (node (ref "U$1") (pin "6") (pinfunction "OUT_6_6") (pintype "output"))
    )
    (net (code "29") (name "Net-(IC1-I4)") (class "Default")
      (node (ref "IC1") (pin "4") (pinfunction "I4_4") (pintype "input"))
      (node (ref "R12") (pin "1") (pinfunction "1_1") (pintype "passive"))
      (node (ref "U$1") (pin "5") (pinfunction "OUT_5_5") (pintype "output"))
    )
    (net (code "30") (name "Net-(IC1-I5)") (class "Default")
      (node (ref "IC1") (pin "5") (pinfunction "I5_5") (pintype "input"))
      (node (ref "R13") (pin "1") (pinfunction "1_1") (pintype "passive"))
      (node (ref "U$1") (pin "4") (pinfunction "OUT_4_4") (pintype "output"))
    )
    (net (code "31") (name "Net-(IC1-I6)") (class "Default")
      (node (ref "IC1") (pin "6") (pinfunction "I6_6") (pintype "input"))
      (node (ref "R14") (pin "1") (pinfunction "1_1") (pintype "passive"))
      (node (ref "U$1") (pin "3") (pinfunction "OUT_3_3") (pintype "output"))
    )
    (net (code "32") (name "Net-(IC1-I7)") (class "Default")
      (node (ref "IC1") (pin "7") (pinfunction "I7_7") (pintype "input"))
      (node (ref "R15") (pin "1") (pinfunction "1_1") (pintype "passive"))
      (node (ref "U$1") (pin "2") (pinfunction "OUT_2_2") (pintype "output"))
    )
    (net (code "33") (name "Net-(IC1-I8)") (class "Default")
      (node (ref "IC1") (pin "8") (pinfunction "I8_8") (pintype "input"))
      (node (ref "R16") (pin "1") (pinfunction "1_1") (pintype "passive"))
      (node (ref "U$1") (pin "1") (pinfunction "OUT_1_1") (pintype "output"))
    )
    (net (code "34") (name "Net-(IC1-O1)") (class "Default")
      (node (ref "IC1") (pin "18") (pinfunction "O1_18") (pintype "open_collector"))
      (node (ref "IC4") (pin "1") (pinfunction "EN/PWM_1") (pintype "input"))
      (node (ref "R1") (pin "1") (pinfunction "1_1") (pintype "passive"))
    )
    (net (code "35") (name "Net-(IC1-O2)") (class "Default")
      (node (ref "IC1") (pin "17") (pinfunction "O2_17") (pintype "open_collector"))
      (node (ref "IC13") (pin "1") (pinfunction "EN/PWM_1") (pintype "input"))
      (node (ref "R42") (pin "1") (pinfunction "1_1") (pintype "passive"))
    )
    (net (code "36") (name "Net-(IC1-O3)") (class "Default")
      (node (ref "IC1") (pin "16") (pinfunction "O3_16") (pintype "open_collector"))
      (node (ref "IC12") (pin "1") (pinfunction "EN/PWM_1") (pintype "input"))
      (node (ref "R38") (pin "1") (pinfunction "1_1") (pintype "passive"))
    )
    (net (code "37") (name "Net-(IC1-O4)") (class "Default")
      (node (ref "IC1") (pin "15") (pinfunction "O4_15") (pintype "open_collector"))
      (node (ref "IC11") (pin "1") (pinfunction "EN/PWM_1") (pintype "input"))
      (node (ref "R34") (pin "1") (pinfunction "1_1") (pintype "passive"))
    )
    (net (code "38") (name "Net-(IC1-O5)") (class "Default")
      (node (ref "IC1") (pin "14") (pinfunction "O5_14") (pintype "open_collector"))
      (node (ref "IC10") (pin "1") (pinfunction "EN/PWM_1") (pintype "input"))
      (node (ref "R30") (pin "1") (pinfunction "1_1") (pintype "passive"))
    )
    (net (code "39") (name "Net-(IC1-O6)") (class "Default")
      (node (ref "IC1") (pin "13") (pinfunction "O6_13") (pintype "open_collector"))
      (node (ref "IC9") (pin "1") (pinfunction "EN/PWM_1") (pintype "input"))
      (node (ref "R24") (pin "1") (pinfunction "1_1") (pintype "passive"))
    )
    (net (code "40") (name "Net-(IC1-O7)") (class "Default")
      (node (ref "IC1") (pin "12") (pinfunction "O7_12") (pintype "open_collector"))
      (node (ref "IC8") (pin "1") (pinfunction "EN/PWM_1") (pintype "input"))
      (node (ref "R20") (pin "1") (pinfunction "1_1") (pintype "passive"))
    )
    (net (code "41") (name "Net-(IC1-O8)") (class "Default")
      (node (ref "IC1") (pin "11") (pinfunction "O8_11") (pintype "open_collector"))
      (node (ref "IC7") (pin "1") (pinfunction "EN/PWM_1") (pintype "input"))
      (node (ref "R11") (pin "1") (pinfunction "1_1") (pintype "passive"))
    )
    (net (code "42") (name "Net-(IC3-(INT1)PD3)") (class "Default")
      (node (ref "IC3") (pin "5") (pinfunction "(INT1)PD3_5") (pintype "bidirectional"))
      (node (ref "U$1") (pin "18") (pinfunction "GSCLK_18") (pintype "input"))
    )
    (net (code "43") (name "Net-(IC3-(MOSI)PB3)") (class "Default")
      (node (ref "IC3") (pin "17") (pinfunction "(MOSI)PB3_17") (pintype "bidirectional"))
      (node (ref "U$1") (pin "26") (pinfunction "SIN_26") (pintype "input"))
    )
    (net (code "44") (name "Net-(IC3-(OC1)PB1)") (class "Default")
      (node (ref "IC3") (pin "15") (pinfunction "(OC1)PB1_15") (pintype "bidirectional"))
      (node (ref "U$1") (pin "24") (pinfunction "XLAT_24") (pintype "input"))
    )
    (net (code "45") (name "Net-(IC3-(RXD)PD0)") (class "Default")
      (node (ref "IC3") (pin "2") (pinfunction "(RXD)PD0_2") (pintype "bidirectional"))
      (node (ref "IC6") (pin "8") (pinfunction "O_8") (pintype "output"))
    )
    (net (code "46") (name "Net-(IC3-(SCK)PB5)") (class "Default")
      (node (ref "IC3") (pin "19") (pinfunction "(SCK)PB5_19") (pintype "bidirectional"))
      (node (ref "STATUSLED") (pin "A") (pinfunction "A_A") (pintype "passive"))
      (node (ref "U$1") (pin "25") (pinfunction "SCLK_25") (pintype "input"))
    )
    (net (code "47") (name "Net-(IC3-(SS)PB2)") (class "Default")
      (node (ref "IC3") (pin "16") (pinfunction "(SS)PB2_16") (pintype "bidirectional"))
      (node (ref "R8") (pin "2") (pinfunction "2_2") (pintype "passive"))
      (node (ref "U$1") (pin "23") (pinfunction "BLANK_23") (pintype "input"))
    )
    (net (code "48") (name "Net-(IC3-XTAL1)") (class "Default")
      (node (ref "C12") (pin "2") (pinfunction "2_2") (pintype "passive"))
      (node (ref "IC3") (pin "9") (pinfunction "XTAL1_9") (pintype "bidirectional"))
      (node (ref "Q1") (pin "1") (pinfunction "1_1") (pintype "passive"))
    )
    (net (code "49") (name "Net-(IC3-XTAL2)") (class "Default")
      (node (ref "C11") (pin "2") (pinfunction "2_2") (pintype "passive"))
      (node (ref "IC3") (pin "10") (pinfunction "XTAL2_10") (pintype "bidirectional"))
      (node (ref "Q1") (pin "2") (pinfunction "2_2") (pintype "passive"))
    )
    (net (code "50") (name "Net-(IC4-RSET)") (class "Default")
      (node (ref "IC4") (pin "4") (pinfunction "RSET_4") (pintype "input"))
      (node (ref "R29") (pin "1") (pinfunction "1_1") (pintype "passive"))
    )
    (net (code "51") (name "Net-(IC6A-I)") (class "Default")
      (node (ref "IC6") (pin "13") (pinfunction "I_13") (pintype "input"))
      (node (ref "OK2") (pin "6") (pinfunction "VO_6") (pintype "passive"))
      (node (ref "R6") (pin "2") (pinfunction "2_2") (pintype "passive"))
    )
    (net (code "52") (name "Net-(IC6B-O)") (class "Default")
      (node (ref "IC6") (pin "10") (pinfunction "O_10") (pintype "output"))
      (node (ref "R4") (pin "1") (pinfunction "1_1") (pintype "passive"))
    )
    (net (code "53") (name "Net-(IC7-RSET)") (class "Default")
      (node (ref "IC7") (pin "4") (pinfunction "RSET_4") (pintype "input"))
      (node (ref "R7") (pin "1") (pinfunction "1_1") (pintype "passive"))
    )
    (net (code "54") (name "Net-(IC8-RSET)") (class "Default")
      (node (ref "IC8") (pin "4") (pinfunction "RSET_4") (pintype "input"))
      (node (ref "R18") (pin "1") (pinfunction "1_1") (pintype "passive"))
    )
    (net (code "55") (name "Net-(IC9-RSET)") (class "Default")
      (node (ref "IC9") (pin "4") (pinfunction "RSET_4") (pintype "input"))
      (node (ref "R23") (pin "1") (pinfunction "1_1") (pintype "passive"))
    )
    (net (code "56") (name "Net-(IC10-RSET)") (class "Default")
      (node (ref "IC10") (pin "4") (pinfunction "RSET_4") (pintype "input"))
      (node (ref "R26") (pin "1") (pinfunction "1_1") (pintype "passive"))
    )
    (net (code "57") (name "Net-(IC11-RSET)") (class "Default")
      (node (ref "IC11") (pin "4") (pinfunction "RSET_4") (pintype "input"))
      (node (ref "R33") (pin "1") (pinfunction "1_1") (pintype "passive"))
    )
    (net (code "58") (name "Net-(IC12-RSET)") (class "Default")
      (node (ref "IC12") (pin "4") (pinfunction "RSET_4") (pintype "input"))
      (node (ref "R37") (pin "1") (pinfunction "1_1") (pintype "passive"))
    )
    (net (code "59") (name "Net-(IC13-RSET)") (class "Default")
      (node (ref "IC13") (pin "4") (pinfunction "RSET_4") (pintype "input"))
      (node (ref "R40") (pin "1") (pinfunction "1_1") (pintype "passive"))
    )
    (net (code "60") (name "Net-(KDR16H1-Pad1)") (class "Default")
      (node (ref "KDR16H1") (pin "1") (pinfunction "1_1") (pintype "bidirectional"))
      (node (ref "SV1") (pin "10") (pinfunction "10_10") (pintype "passive"))
    )
    (net (code "61") (name "Net-(KDR16H1-Pad2)") (class "Default")
      (node (ref "KDR16H1") (pin "2") (pinfunction "2_2") (pintype "bidirectional"))
      (node (ref "SV1") (pin "6") (pinfunction "6_6") (pintype "passive"))
    )
    (net (code "62") (name "Net-(KDR16H1-Pad4)") (class "Default")
      (node (ref "KDR16H1") (pin "4") (pinfunction "4_4") (pintype "bidirectional"))
      (node (ref "SV1") (pin "4") (pinfunction "4_4") (pintype "passive"))
    )
    (net (code "63") (name "Net-(KDR16H1-Pad8)") (class "Default")
      (node (ref "KDR16H1") (pin "8") (pinfunction "8_8") (pintype "bidirectional"))
      (node (ref "SV1") (pin "8") (pinfunction "8_8") (pintype "passive"))
    )
    (net (code "64") (name "Net-(MIDILED-C)") (class "Default")
      (node (ref "MIDILED") (pin "K") (pinfunction "C_K") (pintype "passive"))
      (node (ref "Q2") (pin "3") (pinfunction "D_3") (pintype "passive"))
    )
    (net (code "65") (name "Net-(MIDILED-PadA)") (class "Default")
      (node (ref "MIDILED") (pin "A") (pinfunction "A_A") (pintype "passive"))
      (node (ref "R27") (pin "1") (pinfunction "1_1") (pintype "passive"))
    )
    (net (code "66") (name "Net-(MIDIOUT1-Pad4)") (class "Default")
      (node (ref "MIDIOUT1") (pin "4") (pinfunction "4_4") (pintype "passive"))
      (node (ref "SV1") (pin "7") (pinfunction "7_7") (pintype "passive"))
    )
    (net (code "67") (name "Net-(MIDIOUT1-Pad5)") (class "Default")
      (node (ref "MIDIOUT1") (pin "5") (pinfunction "5_5") (pintype "passive"))
      (node (ref "SV1") (pin "5") (pinfunction "5_5") (pintype "passive"))
    )
    (net (code "68") (name "Net-(OK2-A)") (class "Default")
      (node (ref "OK2") (pin "2") (pinfunction "A_2") (pintype "passive"))
      (node (ref "SV2") (pin "3") (pinfunction "3_3") (pintype "passive"))
    )
    (net (code "69") (name "Net-(OK2-C)") (class "Default")
      (node (ref "OK2") (pin "3") (pinfunction "C_3") (pintype "passive"))
      (node (ref "SV2") (pin "1") (pinfunction "1_1") (pintype "passive"))
    )
    (net (code "70") (name "Net-(POWERLED-C)") (class "Default")
      (node (ref "POWERLED") (pin "K") (pinfunction "C_K") (pintype "passive"))
      (node (ref "R28") (pin "1") (pinfunction "1_1") (pintype "passive"))
    )
    (net (code "71") (name "Net-(POWERLED-PadA)") (class "Default")
      (node (ref "POWERLED") (pin "A") (pinfunction "A_A") (pintype "passive"))
      (node (ref "R27") (pin "2") (pinfunction "2_2") (pintype "passive"))
      (node (ref "SV1") (pin "14") (pinfunction "14_14") (pintype "passive"))
      (node (ref "U$15") (pin "E") (pinfunction "E_E") (pintype "passive"))
    )
    (net (code "72") (name "Net-(Q2-G)") (class "Default")
      (node (ref "Q2") (pin "1") (pinfunction "G_1") (pintype "passive"))
      (node (ref "R41") (pin "2") (pinfunction "2_2") (pintype "passive"))
    )
    (net (code "73") (name "Net-(Q2-S)") (class "Default")
      (node (ref "KDR16H1") (pin "C1") (pinfunction "C1_C1") (pintype "bidirectional"))
      (node (ref "KDR16H1") (pin "C2") (pinfunction "C2_C2") (pintype "bidirectional"))
      (node (ref "MIDIOUT1") (pin "2") (pinfunction "2_2") (pintype "passive"))
      (node (ref "Q2") (pin "2") (pinfunction "S_2") (pintype "passive"))
      (node (ref "R28") (pin "2") (pinfunction "2_2") (pintype "passive"))
      (node (ref "SV1") (pin "2") (pinfunction "2_2") (pintype "passive"))
      (node (ref "U$15") (pin "A") (pinfunction "A_A") (pintype "passive"))
    )
    (net (code "74") (name "Net-(R3-Pad1)") (class "Default")
      (node (ref "R3") (pin "1") (pinfunction "1_1") (pintype "passive"))
      (node (ref "SV2") (pin "7") (pinfunction "7_7") (pintype "passive"))
    )
    (net (code "75") (name "Net-(R4-Pad2)") (class "Default")
      (node (ref "R4") (pin "2") (pinfunction "2_2") (pintype "passive"))
      (node (ref "SV2") (pin "5") (pinfunction "5_5") (pintype "passive"))
    )
    (net (code "76") (name "Net-(R36-Pad2)") (class "Default")
      (node (ref "R36") (pin "2") (pinfunction "2_2") (pintype "passive"))
      (node (ref "SV1") (pin "3") (pinfunction "3_3") (pintype "passive"))
    )
    (net (code "77") (name "Net-(R41-Pad1)") (class "Default")
      (node (ref "R41") (pin "1") (pinfunction "1_1") (pintype "passive"))
      (node (ref "SV1") (pin "9") (pinfunction "9_9") (pintype "passive"))
    )
    (net (code "78") (name "Net-(STATUSLED-C)") (class "Default")
      (node (ref "R22") (pin "1") (pinfunction "1_1") (pintype "passive"))
      (node (ref "STATUSLED") (pin "K") (pinfunction "C_K") (pintype "passive"))
    )
    (net (code "79") (name "Net-(SV1-Pad11)") (class "Default")
      (node (ref "SV1") (pin "11") (pinfunction "11_11") (pintype "passive"))
      (node (ref "U$15") (pin "S") (pinfunction "S_S") (pintype "passive"))
    )
    (net (code "80") (name "Net-(U$1-IREF)") (class "Default")
      (node (ref "R2") (pin "2") (pinfunction "2_2") (pintype "passive"))
      (node (ref "U$1") (pin "20") (pinfunction "IREF_20") (pintype "power_in"))
    )
    (net (code "81") (name "POTI-ARDUINO") (class "Default")
      (node (ref "IC3") (pin "27") (pinfunction "(ADC4)PC4_27") (pintype "bidirectional"))
      (node (ref "SV2") (pin "11") (pinfunction "11_11") (pintype "passive"))
    )
    (net (code "82") (name "RESET") (class "Default")
      (node (ref "IC3") (pin "1") (pinfunction "RESET_1") (pintype "input"))
      (node (ref "J1") (pin "2") (pinfunction "S_2") (pintype "passive"))
      (node (ref "R19") (pin "1") (pinfunction "1_1") (pintype "passive"))
    )
    (net (code "83") (name "VCC") (class "Default")
      (node (ref "5V") (pin "1") (pinfunction "1_1") (pintype "passive"))
      (node (ref "C17") (pin "1") (pinfunction "1_1") (pintype "passive"))
      (node (ref "C3") (pin "+") (pinfunction "+_+") (pintype "passive"))
      (node (ref "IC2") (pin "1") (pinfunction "VI_1") (pintype "input"))
      (node (ref "J2") (pin "1") (pinfunction "S_1") (pintype "passive"))
      (node (ref "J3") (pin "1") (pinfunction "S_1") (pintype "passive"))
      (node (ref "J4") (pin "1") (pinfunction "S_1") (pintype "passive"))
      (node (ref "J5") (pin "1") (pinfunction "S_1") (pintype "passive"))
      (node (ref "J6") (pin "1") (pinfunction "S_1") (pintype "passive"))
      (node (ref "J7") (pin "1") (pinfunction "S_1") (pintype "passive"))
      (node (ref "J8") (pin "1") (pinfunction "S_1") (pintype "passive"))
      (node (ref "J9") (pin "1") (pinfunction "S_1") (pintype "passive"))
      (node (ref "R17") (pin "2") (pinfunction "2_2") (pintype "passive"))
      (node (ref "R21") (pin "2") (pinfunction "2_2") (pintype "passive"))
      (node (ref "R25") (pin "2") (pinfunction "2_2") (pintype "passive"))
      (node (ref "R32") (pin "2") (pinfunction "2_2") (pintype "passive"))
      (node (ref "R35") (pin "2") (pinfunction "2_2") (pintype "passive"))
      (node (ref "R39") (pin "2") (pinfunction "2_2") (pintype "passive"))
      (node (ref "R43") (pin "2") (pinfunction "2_2") (pintype "passive"))
      (node (ref "R5") (pin "2") (pinfunction "2_2") (pintype "passive"))
    )
    (net (code "84") (name "unconnected-(IC3-(ADC0)PC0)-Pad23)") (class "Default")
      (node (ref "IC3") (pin "23") (pinfunction "(ADC0)PC0)_23") (pintype "bidirectional"))
    )
    (net (code "85") (name "unconnected-(IC3-(ADC1)PC1-Pad24)") (class "Default")
      (node (ref "IC3") (pin "24") (pinfunction "(ADC1)PC1_24") (pintype "bidirectional"))
    )
    (net (code "86") (name "unconnected-(IC3-(ADC2)PC2-Pad25)") (class "Default")
      (node (ref "IC3") (pin "25") (pinfunction "(ADC2)PC2_25") (pintype "bidirectional"))
    )
    (net (code "87") (name "unconnected-(IC3-(ADC3)PC3-Pad26)") (class "Default")
      (node (ref "IC3") (pin "26") (pinfunction "(ADC3)PC3_26") (pintype "bidirectional"))
    )
    (net (code "88") (name "unconnected-(IC3-(ADC5)PC5-Pad28)") (class "Default")
      (node (ref "IC3") (pin "28") (pinfunction "(ADC5)PC5_28") (pintype "bidirectional"))
    )
    (net (code "89") (name "unconnected-(IC3-(ICP)PB0-Pad14)") (class "Default")
      (node (ref "IC3") (pin "14") (pinfunction "(ICP)PB0_14") (pintype "bidirectional"))
    )
    (net (code "90") (name "unconnected-(IC3-(MISO)PB4-Pad18)") (class "Default")
      (node (ref "IC3") (pin "18") (pinfunction "(MISO)PB4_18") (pintype "bidirectional"))
    )
    (net (code "91") (name "unconnected-(IC3-(T1)PD5-Pad11)") (class "Default")
      (node (ref "IC3") (pin "11") (pinfunction "(T1)PD5_11") (pintype "bidirectional"))
    )
    (net (code "92") (name "unconnected-(IC3-(TXD)PD1-Pad3)") (class "Default")
      (node (ref "IC3") (pin "3") (pinfunction "(TXD)PD1_3") (pintype "bidirectional"))
    )
    (net (code "93") (name "unconnected-(IC3-AREF-Pad21)") (class "Default")
      (node (ref "IC3") (pin "21") (pinfunction "AREF_21") (pintype "passive"))
    )
    (net (code "94") (name "unconnected-(IC4-PadTAB)") (class "Default")
      (node (ref "IC4") (pin "TAB") (pinfunction "TAB_TAB") (pintype "passive"))
    )
    (net (code "95") (name "unconnected-(IC7-PadTAB)") (class "Default")
      (node (ref "IC7") (pin "TAB") (pinfunction "TAB_TAB") (pintype "passive"))
    )
    (net (code "96") (name "unconnected-(IC8-PadTAB)") (class "Default")
      (node (ref "IC8") (pin "TAB") (pinfunction "TAB_TAB") (pintype "passive"))
    )
    (net (code "97") (name "unconnected-(IC9-PadTAB)") (class "Default")
      (node (ref "IC9") (pin "TAB") (pinfunction "TAB_TAB") (pintype "passive"))
    )
    (net (code "98") (name "unconnected-(IC10-PadTAB)") (class "Default")
      (node (ref "IC10") (pin "TAB") (pinfunction "TAB_TAB") (pintype "passive"))
    )
    (net (code "99") (name "unconnected-(IC11-PadTAB)") (class "Default")
      (node (ref "IC11") (pin "TAB") (pinfunction "TAB_TAB") (pintype "passive"))
    )
    (net (code "100") (name "unconnected-(IC12-PadTAB)") (class "Default")
      (node (ref "IC12") (pin "TAB") (pinfunction "TAB_TAB") (pintype "passive"))
    )
    (net (code "101") (name "unconnected-(IC13-PadTAB)") (class "Default")
      (node (ref "IC13") (pin "TAB") (pinfunction "TAB_TAB") (pintype "passive"))
    )
    (net (code "102") (name "unconnected-(MIDIIN1-Pad1)") (class "Default")
      (node (ref "MIDIIN1") (pin "1") (pinfunction "1_1") (pintype "passive"))
    )
    (net (code "103") (name "unconnected-(MIDIIN1-Pad2)") (class "Default")
      (node (ref "MIDIIN1") (pin "2") (pinfunction "2_2") (pintype "passive"))
    )
    (net (code "104") (name "unconnected-(MIDIIN1-Pad3)") (class "Default")
      (node (ref "MIDIIN1") (pin "3") (pinfunction "3_3") (pintype "passive"))
    )
    (net (code "105") (name "unconnected-(MIDIOUT1-Pad1)") (class "Default")
      (node (ref "MIDIOUT1") (pin "1") (pinfunction "1_1") (pintype "passive"))
    )
    (net (code "106") (name "unconnected-(MIDIOUT1-Pad3)") (class "Default")
      (node (ref "MIDIOUT1") (pin "3") (pinfunction "3_3") (pintype "passive"))
    )
    (net (code "107") (name "unconnected-(OK2-VE-Pad7)") (class "Default")
      (node (ref "OK2") (pin "7") (pinfunction "VE_7") (pintype "passive"))
    )
    (net (code "108") (name "unconnected-(SV1-Pad12)") (class "Default")
      (node (ref "SV1") (pin "12") (pinfunction "12_12") (pintype "passive"))
    )
    (net (code "109") (name "unconnected-(SV1-Pad13)") (class "Default")
      (node (ref "SV1") (pin "13") (pinfunction "13_13") (pintype "passive"))
    )
    (net (code "110") (name "unconnected-(SV2-Pad12)") (class "Default")
      (node (ref "SV2") (pin "12") (pinfunction "12_12") (pintype "passive"))
    )
    (net (code "111") (name "unconnected-(SV2-Pad13)") (class "Default")
      (node (ref "SV2") (pin "13") (pinfunction "13_13") (pintype "passive"))
    )
    (net (code "112") (name "unconnected-(U$1-OUT_0-Pad28)") (class "Default")
      (node (ref "U$1") (pin "28") (pinfunction "OUT_0_28") (pintype "output"))
    )
    (net (code "113") (name "unconnected-(U$1-OUT_9-Pad9)") (class "Default")
      (node (ref "U$1") (pin "9") (pinfunction "OUT_9_9") (pintype "output"))
    )
    (net (code "114") (name "unconnected-(U$1-OUT_10-Pad10)") (class "Default")
      (node (ref "U$1") (pin "10") (pinfunction "OUT_10_10") (pintype "output"))
    )
    (net (code "115") (name "unconnected-(U$1-OUT_11-Pad11)") (class "Default")
      (node (ref "U$1") (pin "11") (pinfunction "OUT_11_11") (pintype "output"))
    )
    (net (code "116") (name "unconnected-(U$1-OUT_12-Pad12)") (class "Default")
      (node (ref "U$1") (pin "12") (pinfunction "OUT_12_12") (pintype "output"))
    )
    (net (code "117") (name "unconnected-(U$1-OUT_13-Pad13)") (class "Default")
      (node (ref "U$1") (pin "13") (pinfunction "OUT_13_13") (pintype "output"))
    )
    (net (code "118") (name "unconnected-(U$1-OUT_14-Pad14)") (class "Default")
      (node (ref "U$1") (pin "14") (pinfunction "OUT_14_14") (pintype "output"))
    )
    (net (code "119") (name "unconnected-(U$1-OUT_15-Pad15)") (class "Default")
      (node (ref "U$1") (pin "15") (pinfunction "OUT_15_15") (pintype "output"))
    )
    (net (code "120") (name "unconnected-(U$1-SOUT-Pad17)") (class "Default")
      (node (ref "U$1") (pin "17") (pinfunction "SOUT_17") (pintype "output"))
    )
    (net (code "121") (name "unconnected-(U$1-XERR-Pad16)") (class "Default")
      (node (ref "U$1") (pin "16") (pinfunction "XERR_16") (pintype "output"))
    )
  )
)
